# Schematic_Altium.net
KiCad netlist of a schematic drawn in Altium Designer
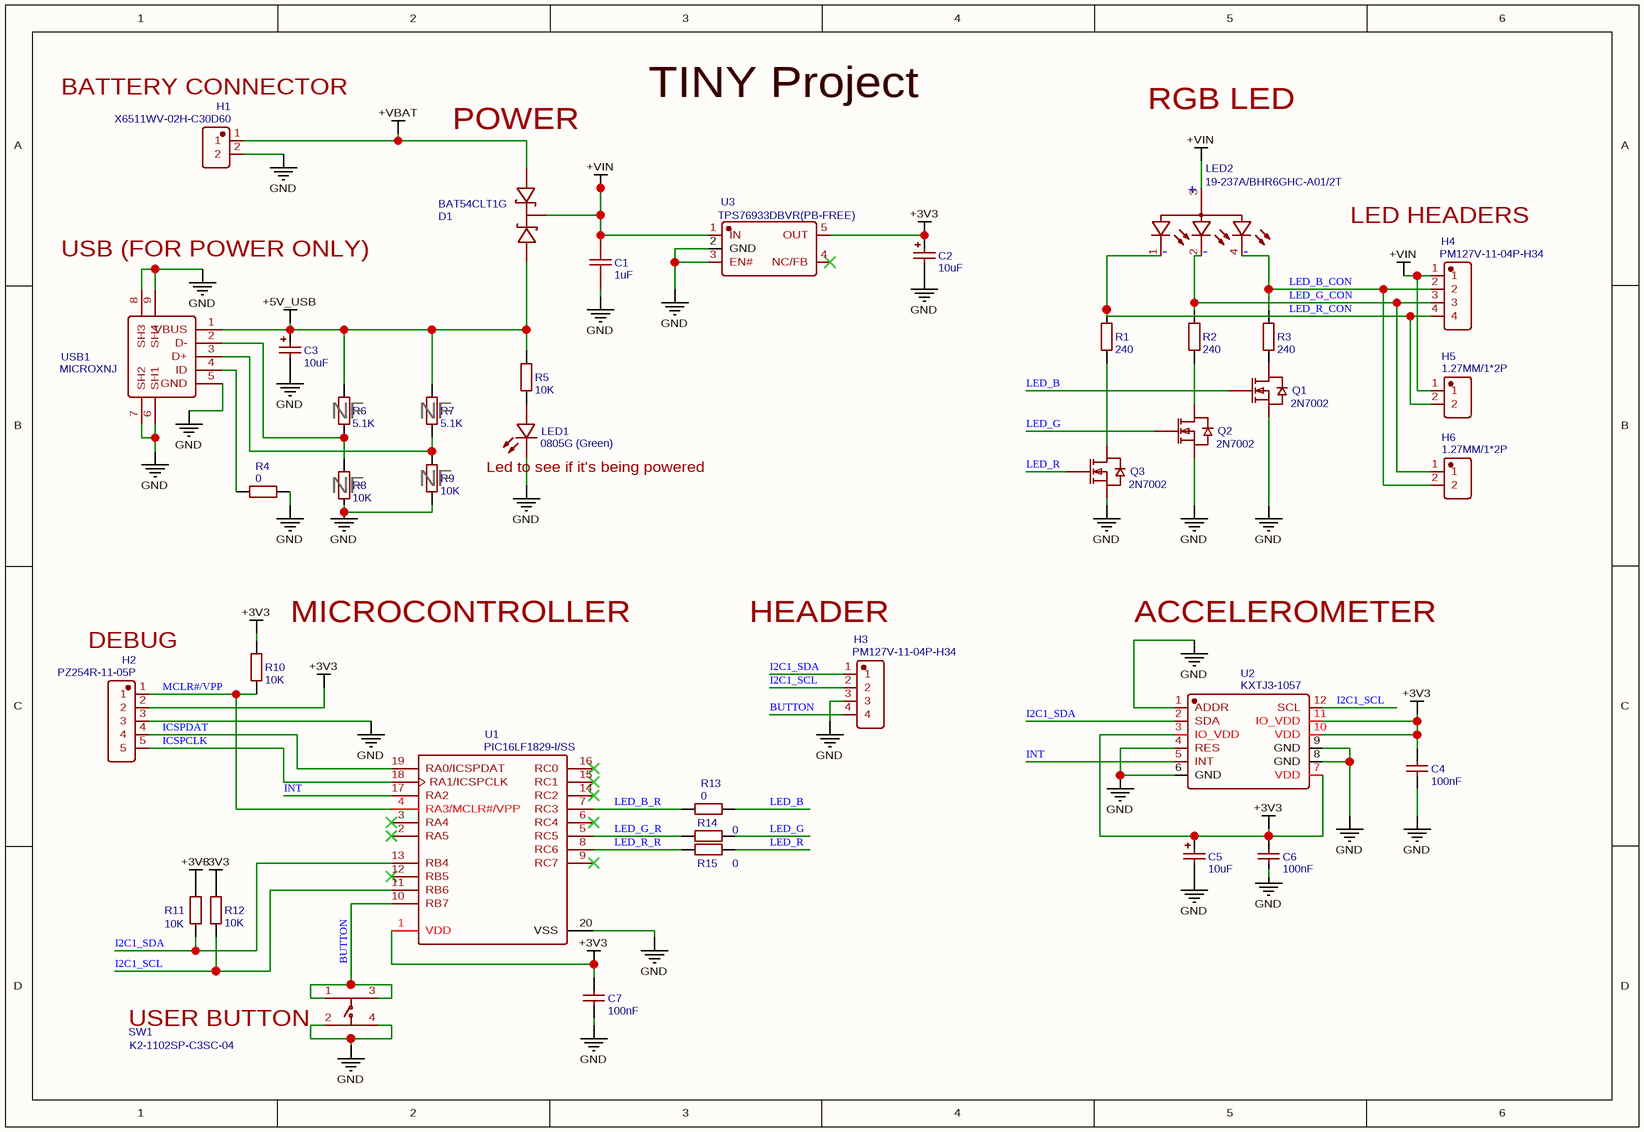
[diagram p0: Schematic(Altium).schdoc]

(export (version "E")
  (design (tool "Eeschema 10.0.6"))
  (components
    (comp (ref "C1")
      (value "1uF")
      (fields
        (field (name "BOM_MANUFACTURER PART") "CL05A105KA5NQNC")
        (field (name "BOM_SUPPLIER PART") "C52923")
      )
      (libsource (lib "altium-import") (part "root_1_1uF_"))
    )
    (comp (ref "C2")
      (value "10uF")
      (fields
        (field (name "BOM_MANUFACTURER PART") "TAJA106K016RNJ")
        (field (name "BOM_SUPPLIER PART") "C7171")
      )
      (libsource (lib "altium-import") (part "root_1_10uF_"))
    )
    (comp (ref "C3")
      (value "10uF")
      (fields
        (field (name "BOM_MANUFACTURER PART") "TAJA106K016RNJ")
        (field (name "BOM_SUPPLIER PART") "C7171")
      )
      (libsource (lib "altium-import") (part "root_1_10uF_"))
    )
    (comp (ref "C4")
      (value "100nF")
      (fields
        (field (name "BOM_MANUFACTURER PART") "CL05B104KO5NNNC")
        (field (name "BOM_SUPPLIER PART") "C1525")
      )
      (libsource (lib "altium-import") (part "root_1_100nF_"))
    )
    (comp (ref "C5")
      (value "10uF")
      (fields
        (field (name "BOM_MANUFACTURER PART") "TAJA106K016RNJ")
        (field (name "BOM_SUPPLIER PART") "C7171")
      )
      (libsource (lib "altium-import") (part "root_1_10uF_"))
    )
    (comp (ref "C6")
      (value "100nF")
      (fields
        (field (name "BOM_MANUFACTURER PART") "CL05B104KO5NNNC")
        (field (name "BOM_SUPPLIER PART") "C1525")
      )
      (libsource (lib "altium-import") (part "root_1_100nF_"))
    )
    (comp (ref "C7")
      (value "100nF")
      (fields
        (field (name "BOM_MANUFACTURER PART") "CL05B104KO5NNNC")
        (field (name "BOM_SUPPLIER PART") "C1525")
      )
      (libsource (lib "altium-import") (part "root_1_100nF_"))
    )
    (comp (ref "D1")
      (value "BAT54CLT1G")
      (fields (field (name "BOM_SUPPLIER PART") "C14308"))
      (libsource (lib "altium-import") (part "root_1_BAT54CLT1G_"))
    )
    (comp (ref "H1")
      (value "X6511WV-02H-C30D60")
      (fields (field (name "BOM_SUPPLIER PART") "C706874") (field (name "CONTRIBUTOR") "LCSC"))
      (libsource (lib "altium-import") (part "root_0_X6511WV-02H-C30D60_"))
    )
    (comp (ref "H2")
      (value "PZ254R-11-05P")
      (fields (field (name "BOM_SUPPLIER PART") "C492413") (field (name "CONTRIBUTOR") "LCSC"))
      (libsource (lib "altium-import") (part "root_0_PZ254R-11-05P_"))
    )
    (comp (ref "H3")
      (value "PM127V-11-04P-H34")
      (fields (field (name "BOM_SUPPLIER PART") "C492398") (field (name "CONTRIBUTOR") "LCSC"))
      (libsource (lib "altium-import") (part "root_0_PM127V-11-04P-H34_"))
    )
    (comp (ref "H4")
      (value "PM127V-11-04P-H34")
      (fields (field (name "BOM_SUPPLIER PART") "C492398") (field (name "CONTRIBUTOR") "LCSC"))
      (libsource (lib "altium-import") (part "root_0_PM127V-11-04P-H34_"))
    )
    (comp (ref "H5")
      (value "1.27MM/1*2P")
      (fields
        (field (name "BOM_SUPPLIER PART") "C703015")
        (field (name "BOM_MANUFACTURER PART") "1.27mm/1*2P")
        (field (name "CONTRIBUTOR") "LCSC")
      )
      (libsource (lib "altium-import") (part "root_0_1.27MM/1*2P_"))
    )
    (comp (ref "H6")
      (value "1.27MM/1*2P")
      (fields
        (field (name "BOM_SUPPLIER PART") "C703015")
        (field (name "BOM_MANUFACTURER PART") "1.27mm/1*2P")
        (field (name "CONTRIBUTOR") "LCSC")
      )
      (libsource (lib "altium-import") (part "root_0_1.27MM/1*2P_"))
    )
    (comp (ref "LED1")
      (value "0805G (Green)")
      (fields (field (name "BOM_SUPPLIER PART") "C2297"))
      (libsource (lib "altium-import") (part "root_1_0805G (Green)_"))
    )
    (comp (ref "LED2")
      (value "19-237A/BHR6GHC-A01/2T")
      (fields (field (name "BOM_SUPPLIER PART") "C114830") (field (name "CONTRIBUTOR") "LCSC"))
      (libsource (lib "altium-import") (part "root_0_19-237A/BHR6GHC-A01/2T_"))
    )
    (comp (ref "Q1")
      (value "2N7002")
      (fields (field (name "BOM_SUPPLIER PART") "C8545"))
      (libsource (lib "altium-import") (part "root_0_2N7002_"))
    )
    (comp (ref "Q2")
      (value "2N7002")
      (fields (field (name "BOM_SUPPLIER PART") "C8545"))
      (libsource (lib "altium-import") (part "root_0_2N7002_"))
    )
    (comp (ref "Q3")
      (value "2N7002")
      (fields (field (name "BOM_SUPPLIER PART") "C8545"))
      (libsource (lib "altium-import") (part "root_0_2N7002_"))
    )
    (comp (ref "R1")
      (value "240")
      (fields
        (field (name "BOM_MANUFACTURER PART") "0402WGF2400TCE")
        (field (name "BOM_SUPPLIER PART") "C25094")
      )
      (libsource (lib "altium-import") (part "root_1_240_"))
    )
    (comp (ref "R2")
      (value "240")
      (fields
        (field (name "BOM_MANUFACTURER PART") "0402WGF2400TCE")
        (field (name "BOM_SUPPLIER PART") "C25094")
      )
      (libsource (lib "altium-import") (part "root_1_240_"))
    )
    (comp (ref "R3")
      (value "240")
      (fields
        (field (name "BOM_MANUFACTURER PART") "0402WGF2400TCE")
        (field (name "BOM_SUPPLIER PART") "C25094")
      )
      (libsource (lib "altium-import") (part "root_1_240_"))
    )
    (comp (ref "R4")
      (value "0")
      (fields
        (field (name "BOM_MANUFACTURER PART") "0402WGF0000TCE")
        (field (name "BOM_SUPPLIER PART") "C17168")
      )
      (libsource (lib "altium-import") (part "root_0_0_"))
    )
    (comp (ref "R5")
      (value "10K")
      (fields
        (field (name "BOM_MANUFACTURER PART") "0402WGF1002TCE")
        (field (name "BOM_SUPPLIER PART") "C25744")
      )
      (libsource (lib "altium-import") (part "root_1_10K_"))
    )
    (comp (ref "R6")
      (value "5.1K")
      (fields
        (field (name "BOM_MANUFACTURER PART") "0402WGF5101TCE")
        (field (name "BOM_SUPPLIER PART") "C25905")
      )
      (libsource (lib "altium-import") (part "root_1_5.1K_"))
    )
    (comp (ref "R7")
      (value "5.1K")
      (fields
        (field (name "BOM_MANUFACTURER PART") "0402WGF5101TCE")
        (field (name "BOM_SUPPLIER PART") "C25905")
      )
      (libsource (lib "altium-import") (part "root_1_5.1K_"))
    )
    (comp (ref "R8")
      (value "10K")
      (fields
        (field (name "BOM_MANUFACTURER PART") "0402WGF1002TCE")
        (field (name "BOM_SUPPLIER PART") "C25744")
      )
      (libsource (lib "altium-import") (part "root_1_10K_"))
    )
    (comp (ref "R9")
      (value "10K")
      (fields
        (field (name "BOM_MANUFACTURER PART") "0402WGF1002TCE")
        (field (name "BOM_SUPPLIER PART") "C25744")
      )
      (libsource (lib "altium-import") (part "root_1_10K_"))
    )
    (comp (ref "R10")
      (value "10K")
      (fields
        (field (name "BOM_MANUFACTURER PART") "0402WGF1002TCE")
        (field (name "BOM_SUPPLIER PART") "C25744")
      )
      (libsource (lib "altium-import") (part "root_1_10K_"))
    )
    (comp (ref "R11")
      (value "10K")
      (fields
        (field (name "BOM_MANUFACTURER PART") "0402WGF1002TCE")
        (field (name "BOM_SUPPLIER PART") "C25744")
      )
      (libsource (lib "altium-import") (part "root_1_10K_"))
    )
    (comp (ref "R12")
      (value "10K")
      (fields
        (field (name "BOM_MANUFACTURER PART") "0402WGF1002TCE")
        (field (name "BOM_SUPPLIER PART") "C25744")
      )
      (libsource (lib "altium-import") (part "root_1_10K_"))
    )
    (comp (ref "R13")
      (value "0")
      (fields
        (field (name "BOM_MANUFACTURER PART") "0402WGF0000TCE")
        (field (name "BOM_SUPPLIER PART") "C17168")
      )
      (libsource (lib "altium-import") (part "root_0_0_"))
    )
    (comp (ref "R14")
      (value "0")
      (fields
        (field (name "BOM_MANUFACTURER PART") "0402WGF0000TCE")
        (field (name "BOM_SUPPLIER PART") "C17168")
      )
      (libsource (lib "altium-import") (part "root_0_0_"))
    )
    (comp (ref "R15")
      (value "0")
      (fields
        (field (name "BOM_MANUFACTURER PART") "0402WGF0000TCE")
        (field (name "BOM_SUPPLIER PART") "C17168")
      )
      (libsource (lib "altium-import") (part "root_0_0_"))
    )
    (comp (ref "SW1")
      (value "K2-1102SP-C3SC-04")
      (fields (field (name "BOM_SUPPLIER PART") "C707347") (field (name "CONTRIBUTOR") "LCSC"))
      (libsource (lib "altium-import") (part "root_0_K2-1102SP-C3SC-04_"))
    )
    (comp (ref "U1")
      (value "PIC16LF1829-I/SS")
      (fields (field (name "BOM_SUPPLIER PART") "C59149"))
      (libsource (lib "altium-import") (part "root_0_PIC16LF1829-I/SS_"))
    )
    (comp (ref "U2")
      (value "KXTJ3-1057")
      (fields (field (name "BOM_SUPPLIER PART") "C442603") (field (name "CONTRIBUTOR") "LCSC"))
      (libsource (lib "altium-import") (part "root_0_KXTJ3-1057_"))
    )
    (comp (ref "U3")
      (value "TPS76933DBVR(PB-FREE)")
      (fields (field (name "BOM_SUPPLIER PART") "C7101"))
      (libsource (lib "altium-import") (part "root_0_TPS76933DBVR(PB-FREE)_"))
    )
    (comp (ref "USB1")
      (value "MICROXNJ")
      (fields
        (field (name "BOM_SUPPLIER PART") "C404969")
        (field (name "BOM_MANUFACTURER PART") "MicroXNJ")
        (field (name "CONTRIBUTOR") "LCSC")
      )
      (libsource (lib "altium-import") (part "root_2_MICROXNJ_"))
    )
  )
  (nets
    (net (code "1") (name "+3V3") (class "Default")
      (node (ref "C2") (pin "1") (pinfunction "1_1") (pintype "passive"))
      (node (ref "C4") (pin "2") (pinfunction "2_2") (pintype "passive"))
      (node (ref "C5") (pin "1") (pinfunction "1_1") (pintype "passive"))
      (node (ref "C6") (pin "2") (pinfunction "2_2") (pintype "passive"))
      (node (ref "C7") (pin "2") (pinfunction "2_2") (pintype "passive"))
      (node (ref "H2") (pin "2") (pinfunction "2_2") (pintype "passive"))
      (node (ref "R10") (pin "2") (pinfunction "2_2") (pintype "passive"))
      (node (ref "R11") (pin "2") (pinfunction "2_2") (pintype "passive"))
      (node (ref "R12") (pin "2") (pinfunction "2_2") (pintype "passive"))
      (node (ref "U1") (pin "1") (pinfunction "VDD_1") (pintype "passive"))
      (node (ref "U2") (pin "10") (pinfunction "VDD_10") (pintype "passive"))
      (node (ref "U2") (pin "11") (pinfunction "IO_VDD_11") (pintype "passive"))
      (node (ref "U2") (pin "3") (pinfunction "IO_VDD_3") (pintype "passive"))
      (node (ref "U2") (pin "7") (pinfunction "VDD_7") (pintype "passive"))
      (node (ref "U3") (pin "5") (pinfunction "OUT_5") (pintype "passive"))
    )
    (net (code "2") (name "+5V_USB") (class "Default")
      (node (ref "C3") (pin "1") (pinfunction "1_1") (pintype "passive"))
      (node (ref "D1") (pin "2") (pinfunction "A_2") (pintype "passive"))
      (node (ref "R5") (pin "2") (pinfunction "2_2") (pintype "passive"))
      (node (ref "R6") (pin "2") (pinfunction "2_2") (pintype "passive"))
      (node (ref "R7") (pin "2") (pinfunction "2_2") (pintype "passive"))
      (node (ref "USB1") (pin "1") (pinfunction "VBUS_1") (pintype "passive"))
    )
    (net (code "3") (name "+VBAT") (class "Default")
      (node (ref "D1") (pin "1") (pinfunction "A_1") (pintype "passive"))
      (node (ref "H1") (pin "1") (pinfunction "1_1") (pintype "passive"))
    )
    (net (code "4") (name "+VIN") (class "Default")
      (node (ref "C1") (pin "2") (pinfunction "2_2") (pintype "passive"))
      (node (ref "D1") (pin "3") (pinfunction "K_3") (pintype "passive"))
      (node (ref "H4") (pin "1") (pinfunction "1_1") (pintype "passive"))
      (node (ref "H5") (pin "1") (pinfunction "1_1") (pintype "passive"))
      (node (ref "LED2") (pin "3") (pinfunction "3_3") (pintype "passive"))
      (node (ref "U3") (pin "1") (pinfunction "IN_1") (pintype "passive"))
    )
    (net (code "5") (name "/BUTTON") (class "Default")
      (node (ref "H3") (pin "4") (pinfunction "4_4") (pintype "passive"))
      (node (ref "SW1") (pin "1") (pinfunction "1_1") (pintype "passive"))
      (node (ref "SW1") (pin "3") (pinfunction "3_3") (pintype "passive"))
      (node (ref "U1") (pin "10") (pinfunction "RB7_10") (pintype "passive"))
    )
    (net (code "6") (name "/I2C1_SCL") (class "Default")
      (node (ref "H3") (pin "2") (pinfunction "2_2") (pintype "passive"))
      (node (ref "R12") (pin "1") (pinfunction "1_1") (pintype "passive"))
      (node (ref "U1") (pin "11") (pinfunction "RB6_11") (pintype "passive"))
      (node (ref "U2") (pin "12") (pinfunction "SCL_12") (pintype "passive"))
    )
    (net (code "7") (name "/I2C1_SDA") (class "Default")
      (node (ref "H3") (pin "1") (pinfunction "1_1") (pintype "passive"))
      (node (ref "R11") (pin "1") (pinfunction "1_1") (pintype "passive"))
      (node (ref "U1") (pin "13") (pinfunction "RB4_13") (pintype "passive"))
      (node (ref "U2") (pin "2") (pinfunction "SDA_2") (pintype "passive"))
    )
    (net (code "8") (name "/ICSPCLK") (class "Default")
      (node (ref "H2") (pin "5") (pinfunction "5_5") (pintype "passive"))
      (node (ref "U1") (pin "18") (pinfunction "RA1/ICSPCLK_18") (pintype "passive"))
    )
    (net (code "9") (name "/ICSPDAT") (class "Default")
      (node (ref "H2") (pin "4") (pinfunction "4_4") (pintype "passive"))
      (node (ref "U1") (pin "19") (pinfunction "RA0/ICSPDAT_19") (pintype "passive"))
    )
    (net (code "10") (name "/INT") (class "Default")
      (node (ref "U1") (pin "17") (pinfunction "RA2_17") (pintype "passive"))
      (node (ref "U2") (pin "5") (pinfunction "INT_5") (pintype "passive"))
    )
    (net (code "11") (name "/LED_B") (class "Default")
      (node (ref "Q1") (pin "1") (pinfunction "G_1") (pintype "passive"))
      (node (ref "R13") (pin "2") (pinfunction "2_2") (pintype "passive"))
    )
    (net (code "12") (name "/LED_B_CON") (class "Default")
      (node (ref "H4") (pin "2") (pinfunction "2_2") (pintype "passive"))
      (node (ref "H6") (pin "2") (pinfunction "2_2") (pintype "passive"))
      (node (ref "LED2") (pin "4") (pinfunction "4_4") (pintype "passive"))
      (node (ref "R3") (pin "2") (pinfunction "2_2") (pintype "passive"))
    )
    (net (code "13") (name "/LED_B_R") (class "Default")
      (node (ref "R13") (pin "1") (pinfunction "1_1") (pintype "passive"))
      (node (ref "U1") (pin "7") (pinfunction "RC3_7") (pintype "passive"))
    )
    (net (code "14") (name "/LED_G") (class "Default")
      (node (ref "Q2") (pin "1") (pinfunction "G_1") (pintype "passive"))
      (node (ref "R14") (pin "2") (pinfunction "2_2") (pintype "passive"))
    )
    (net (code "15") (name "/LED_G_CON") (class "Default")
      (node (ref "H4") (pin "3") (pinfunction "3_3") (pintype "passive"))
      (node (ref "H6") (pin "1") (pinfunction "1_1") (pintype "passive"))
      (node (ref "LED2") (pin "2") (pinfunction "2_2") (pintype "passive"))
      (node (ref "R2") (pin "2") (pinfunction "2_2") (pintype "passive"))
    )
    (net (code "16") (name "/LED_G_R") (class "Default")
      (node (ref "R14") (pin "1") (pinfunction "1_1") (pintype "passive"))
      (node (ref "U1") (pin "5") (pinfunction "RC5_5") (pintype "passive"))
    )
    (net (code "17") (name "/LED_R") (class "Default")
      (node (ref "Q3") (pin "1") (pinfunction "G_1") (pintype "passive"))
      (node (ref "R15") (pin "2") (pinfunction "2_2") (pintype "passive"))
    )
    (net (code "18") (name "/LED_R_CON") (class "Default")
      (node (ref "H4") (pin "4") (pinfunction "4_4") (pintype "passive"))
      (node (ref "H5") (pin "2") (pinfunction "2_2") (pintype "passive"))
      (node (ref "LED2") (pin "1") (pinfunction "1_1") (pintype "passive"))
      (node (ref "R1") (pin "2") (pinfunction "2_2") (pintype "passive"))
    )
    (net (code "19") (name "/LED_R_R") (class "Default")
      (node (ref "R15") (pin "1") (pinfunction "1_1") (pintype "passive"))
      (node (ref "U1") (pin "8") (pinfunction "RC6_8") (pintype "passive"))
    )
    (net (code "20") (name "/MCLR#{slash}VPP") (class "Default")
      (node (ref "H2") (pin "1") (pinfunction "1_1") (pintype "passive"))
      (node (ref "R10") (pin "1") (pinfunction "1_1") (pintype "passive"))
      (node (ref "U1") (pin "4") (pinfunction "RA3/MCLR#/VPP_4") (pintype "passive"))
    )
    (net (code "21") (name "GND") (class "Default")
      (node (ref "C1") (pin "1") (pinfunction "1_1") (pintype "passive"))
      (node (ref "C2") (pin "2") (pinfunction "2_2") (pintype "passive"))
      (node (ref "C3") (pin "2") (pinfunction "2_2") (pintype "passive"))
      (node (ref "C4") (pin "1") (pinfunction "1_1") (pintype "passive"))
      (node (ref "C5") (pin "2") (pinfunction "2_2") (pintype "passive"))
      (node (ref "C6") (pin "1") (pinfunction "1_1") (pintype "passive"))
      (node (ref "C7") (pin "1") (pinfunction "1_1") (pintype "passive"))
      (node (ref "H1") (pin "2") (pinfunction "2_2") (pintype "passive"))
      (node (ref "H2") (pin "3") (pinfunction "3_3") (pintype "passive"))
      (node (ref "H3") (pin "3") (pinfunction "3_3") (pintype "passive"))
      (node (ref "LED1") (pin "1") (pinfunction "K_1") (pintype "passive"))
      (node (ref "Q1") (pin "2") (pinfunction "S_2") (pintype "passive"))
      (node (ref "Q2") (pin "2") (pinfunction "S_2") (pintype "passive"))
      (node (ref "Q3") (pin "2") (pinfunction "S_2") (pintype "passive"))
      (node (ref "R4") (pin "2") (pinfunction "2_2") (pintype "passive"))
      (node (ref "R8") (pin "1") (pinfunction "1_1") (pintype "passive"))
      (node (ref "R9") (pin "1") (pinfunction "1_1") (pintype "passive"))
      (node (ref "SW1") (pin "2") (pinfunction "2_2") (pintype "passive"))
      (node (ref "SW1") (pin "4") (pinfunction "4_4") (pintype "passive"))
      (node (ref "U1") (pin "20") (pinfunction "VSS_20") (pintype "passive"))
      (node (ref "U2") (pin "1") (pinfunction "ADDR_1") (pintype "passive"))
      (node (ref "U2") (pin "4") (pinfunction "RES_4") (pintype "passive"))
      (node (ref "U2") (pin "6") (pinfunction "GND_6") (pintype "passive"))
      (node (ref "U2") (pin "8") (pinfunction "GND_8") (pintype "passive"))
      (node (ref "U2") (pin "9") (pinfunction "GND_9") (pintype "passive"))
      (node (ref "U3") (pin "2") (pinfunction "GND_2") (pintype "passive"))
      (node (ref "U3") (pin "3") (pinfunction "EN#_3") (pintype "passive"))
      (node (ref "USB1") (pin "5") (pinfunction "GND_5") (pintype "passive"))
      (node (ref "USB1") (pin "6") (pinfunction "SH1_6") (pintype "passive"))
      (node (ref "USB1") (pin "7") (pinfunction "SH2_7") (pintype "passive"))
      (node (ref "USB1") (pin "8") (pinfunction "SH3_8") (pintype "passive"))
      (node (ref "USB1") (pin "9") (pinfunction "SH4_9") (pintype "passive"))
    )
    (net (code "22") (name "Net-(LED1-A)") (class "Default")
      (node (ref "LED1") (pin "2") (pinfunction "A_2") (pintype "passive"))
      (node (ref "R5") (pin "1") (pinfunction "1_1") (pintype "passive"))
    )
    (net (code "23") (name "Net-(Q1-D)") (class "Default")
      (node (ref "Q1") (pin "3") (pinfunction "D_3") (pintype "passive"))
      (node (ref "R3") (pin "1") (pinfunction "1_1") (pintype "passive"))
    )
    (net (code "24") (name "Net-(Q2-D)") (class "Default")
      (node (ref "Q2") (pin "3") (pinfunction "D_3") (pintype "passive"))
      (node (ref "R2") (pin "1") (pinfunction "1_1") (pintype "passive"))
    )
    (net (code "25") (name "Net-(Q3-D)") (class "Default")
      (node (ref "Q3") (pin "3") (pinfunction "D_3") (pintype "passive"))
      (node (ref "R1") (pin "1") (pinfunction "1_1") (pintype "passive"))
    )
    (net (code "26") (name "Net-(USB1-D+)") (class "Default")
      (node (ref "R7") (pin "1") (pinfunction "1_1") (pintype "passive"))
      (node (ref "R9") (pin "2") (pinfunction "2_2") (pintype "passive"))
      (node (ref "USB1") (pin "3") (pinfunction "D+_3") (pintype "passive"))
    )
    (net (code "27") (name "Net-(USB1-D-)") (class "Default")
      (node (ref "R6") (pin "1") (pinfunction "1_1") (pintype "passive"))
      (node (ref "R8") (pin "2") (pinfunction "2_2") (pintype "passive"))
      (node (ref "USB1") (pin "2") (pinfunction "D-_2") (pintype "passive"))
    )
    (net (code "28") (name "Net-(USB1-ID)") (class "Default")
      (node (ref "R4") (pin "1") (pinfunction "1_1") (pintype "passive"))
      (node (ref "USB1") (pin "4") (pinfunction "ID_4") (pintype "passive"))
    )
    (net (code "29") (name "unconnected-(U1-RA4-Pad3)") (class "Default")
      (node (ref "U1") (pin "3") (pinfunction "RA4_3") (pintype "passive+no_connect"))
    )
    (net (code "30") (name "unconnected-(U1-RA5-Pad2)") (class "Default")
      (node (ref "U1") (pin "2") (pinfunction "RA5_2") (pintype "passive+no_connect"))
    )
    (net (code "31") (name "unconnected-(U1-RB5-Pad12)") (class "Default")
      (node (ref "U1") (pin "12") (pinfunction "RB5_12") (pintype "passive+no_connect"))
    )
    (net (code "32") (name "unconnected-(U1-RC0-Pad16)") (class "Default")
      (node (ref "U1") (pin "16") (pinfunction "RC0_16") (pintype "passive+no_connect"))
    )
    (net (code "33") (name "unconnected-(U1-RC1-Pad15)") (class "Default")
      (node (ref "U1") (pin "15") (pinfunction "RC1_15") (pintype "passive+no_connect"))
    )
    (net (code "34") (name "unconnected-(U1-RC2-Pad14)") (class "Default")
      (node (ref "U1") (pin "14") (pinfunction "RC2_14") (pintype "passive+no_connect"))
    )
    (net (code "35") (name "unconnected-(U1-RC4-Pad6)") (class "Default")
      (node (ref "U1") (pin "6") (pinfunction "RC4_6") (pintype "passive+no_connect"))
    )
    (net (code "36") (name "unconnected-(U1-RC7-Pad9)") (class "Default")
      (node (ref "U1") (pin "9") (pinfunction "RC7_9") (pintype "passive+no_connect"))
    )
    (net (code "37") (name "unconnected-(U3-NC{slash}FB-Pad4)") (class "Default")
      (node (ref "U3") (pin "4") (pinfunction "NC/FB_4") (pintype "passive+no_connect"))
    )
  )
)
